# Connectors_and_mechanical.net
KiCad netlist of a schematic drawn in Altium Designer
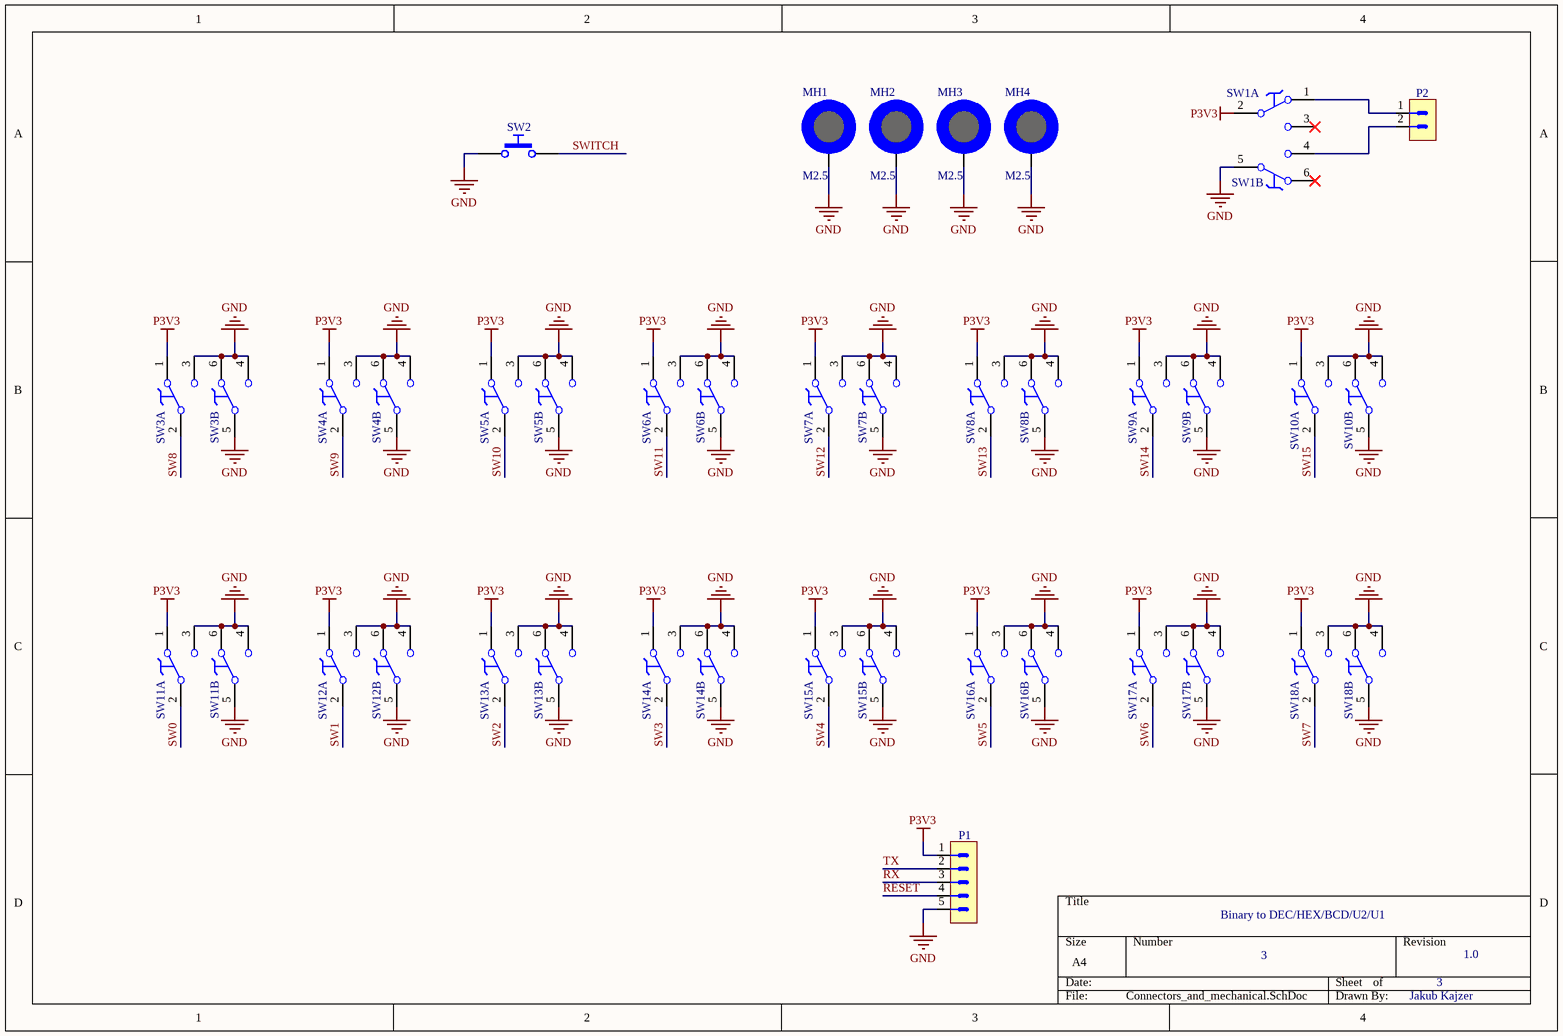
[diagram p0: Connectors_and_mechanical.SchDoc]

(export (version "E")
  (design (tool "Eeschema 10.0.6"))
  (components
    (comp (ref "MH1")
      (value "M2.5")
      (footprint "MH-M2.5_COPPER")
      (description "Mounting hole, M2.5, exposed pad")
      (fields (field (name "AUTHOR") "KB"))
      (libsource (lib "Mechanical And PCB Features") (part "MH"))
    )
    (comp (ref "MH2")
      (value "M2.5")
      (footprint "MH-M2.5_COPPER")
      (description "Mounting hole, M2.5, exposed pad")
      (fields (field (name "AUTHOR") "KB"))
      (libsource (lib "Mechanical And PCB Features") (part "MH"))
    )
    (comp (ref "MH3")
      (value "M2.5")
      (footprint "MH-M2.5_COPPER")
      (description "Mounting hole, M2.5, exposed pad")
      (fields (field (name "AUTHOR") "KB"))
      (libsource (lib "Mechanical And PCB Features") (part "MH"))
    )
    (comp (ref "MH4")
      (value "M2.5")
      (footprint "MH-M2.5_COPPER")
      (description "Mounting hole, M2.5, exposed pad")
      (fields (field (name "AUTHOR") "KB"))
      (libsource (lib "Mechanical And PCB Features") (part "MH"))
    )
    (comp (ref "P1")
      (value "SSW-105-02-G-S")
      (footprint "SAMTEC_SSW-105-02-G-S")
      (description "General Purpose Header: THT, 2.54mm, Female, Straight, Long Lead")
      (fields
        (field (name "MANUFACTURER") "GENERIC")
        (field (name "MANUFACTURER PART NUMBER") "HDR_THT_5X1V_F_2P54MM")
        (field (name "AUTHOR") "UN")
      )
      (libsource (lib "Connectors") (part "Header 5x1"))
    )
    (comp (ref "P2")
      (value "MTLW-102-07-G-S-250")
      (footprint "SAMTEC_MTLW-102-07-G-S-250")
      (description "General Purpose Header: THT, 2.54mm, Male, Straight")
      (fields
        (field (name "MANUFACTURER") "GENERIC")
        (field (name "MANUFACTURER PART NUMBER") "HDR_THT_2X1V_M_2P54MM")
        (field (name "AUTHOR") "PC")
      )
      (libsource (lib "Connectors") (part "Header 2x1"))
    )
    (comp (ref "SW1")
      (value "SS008B")
      (footprint "SS008B-02P-22")
      (description "Switch  2 position; DPDT; 0,3A/30VDC; ON-ON; 50mŁ[")
      (fields
        (field (name "MANUFACTURER") "CANAL ELECTRONIC")
        (field (name "MANUFACTURER PART NUMBER") "SS008B-02P-22")
        (field (name "AUTHOR") "JK")
      )
      (libsource (lib "") (part "SW DPDT 1NC-2C-3NO-4NO-5C-6NC_1"))
    )
    (comp (ref "SW2")
      (value "PTS636")
      (footprint "PTS636_SMT_G")
      (description "Tactile Switches Tact 50mA 12VDC, 6.0x3.5, 4.3mm H, 180gf, G leads, No ground pin, Black Actuator")
      (fields
        (field (name "MANUFACTURER") "C&K")
        (field (name "MANUFACTURER PART NUMBER") "PTS636 SM43 SMTR LFS")
        (field (name "AUTHOR") "KB")
      )
      (libsource (lib "Relays And Switches") (part "PB SPST 1NO-2NO"))
    )
    (comp (ref "SW3")
      (value "SS008B")
      (footprint "SS008B-02P-22")
      (description "Switch  2 position; DPDT; 0,3A/30VDC; ON-ON; 50mŁ[")
      (fields
        (field (name "MANUFACTURER") "CANAL ELECTRONIC")
        (field (name "MANUFACTURER PART NUMBER") "SS008B-02P-22")
        (field (name "AUTHOR") "JK")
      )
      (libsource (lib "Relays And Switches") (part "SW DPDT 1NC-2C-3NO-4NO-5C-6NC"))
    )
    (comp (ref "SW4")
      (value "SS008B")
      (footprint "SS008B-02P-22")
      (description "Switch  2 position; DPDT; 0,3A/30VDC; ON-ON; 50mŁ[")
      (fields
        (field (name "MANUFACTURER") "CANAL ELECTRONIC")
        (field (name "MANUFACTURER PART NUMBER") "SS008B-02P-22")
        (field (name "AUTHOR") "JK")
      )
      (libsource (lib "") (part "SW DPDT 1NC-2C-3NO-4NO-5C-6NC_2"))
    )
    (comp (ref "SW5")
      (value "SS008B")
      (footprint "SS008B-02P-22")
      (description "Switch  2 position; DPDT; 0,3A/30VDC; ON-ON; 50mŁ[")
      (fields
        (field (name "MANUFACTURER") "CANAL ELECTRONIC")
        (field (name "MANUFACTURER PART NUMBER") "SS008B-02P-22")
        (field (name "AUTHOR") "JK")
      )
      (libsource (lib "") (part "SW DPDT 1NC-2C-3NO-4NO-5C-6NC_2"))
    )
    (comp (ref "SW6")
      (value "SS008B")
      (footprint "SS008B-02P-22")
      (description "Switch  2 position; DPDT; 0,3A/30VDC; ON-ON; 50mŁ[")
      (fields
        (field (name "MANUFACTURER") "CANAL ELECTRONIC")
        (field (name "MANUFACTURER PART NUMBER") "SS008B-02P-22")
        (field (name "AUTHOR") "JK")
      )
      (libsource (lib "") (part "SW DPDT 1NC-2C-3NO-4NO-5C-6NC_2"))
    )
    (comp (ref "SW7")
      (value "SS008B")
      (footprint "SS008B-02P-22")
      (description "Switch  2 position; DPDT; 0,3A/30VDC; ON-ON; 50mŁ[")
      (fields
        (field (name "MANUFACTURER") "CANAL ELECTRONIC")
        (field (name "MANUFACTURER PART NUMBER") "SS008B-02P-22")
        (field (name "AUTHOR") "JK")
      )
      (libsource (lib "Relays And Switches") (part "SW DPDT 1NC-2C-3NO-4NO-5C-6NC"))
    )
    (comp (ref "SW8")
      (value "SS008B")
      (footprint "SS008B-02P-22")
      (description "Switch  2 position; DPDT; 0,3A/30VDC; ON-ON; 50mŁ[")
      (fields
        (field (name "MANUFACTURER") "CANAL ELECTRONIC")
        (field (name "MANUFACTURER PART NUMBER") "SS008B-02P-22")
        (field (name "AUTHOR") "JK")
      )
      (libsource (lib "Relays And Switches") (part "SW DPDT 1NC-2C-3NO-4NO-5C-6NC"))
    )
    (comp (ref "SW9")
      (value "SS008B")
      (footprint "SS008B-02P-22")
      (description "Switch  2 position; DPDT; 0,3A/30VDC; ON-ON; 50mŁ[")
      (fields
        (field (name "MANUFACTURER") "CANAL ELECTRONIC")
        (field (name "MANUFACTURER PART NUMBER") "SS008B-02P-22")
        (field (name "AUTHOR") "JK")
      )
      (libsource (lib "Relays And Switches") (part "SW DPDT 1NC-2C-3NO-4NO-5C-6NC"))
    )
    (comp (ref "SW10")
      (value "SS008B")
      (footprint "SS008B-02P-22")
      (description "Switch  2 position; DPDT; 0,3A/30VDC; ON-ON; 50mŁ[")
      (fields
        (field (name "MANUFACTURER") "CANAL ELECTRONIC")
        (field (name "MANUFACTURER PART NUMBER") "SS008B-02P-22")
        (field (name "AUTHOR") "JK")
      )
      (libsource (lib "Relays And Switches") (part "SW DPDT 1NC-2C-3NO-4NO-5C-6NC"))
    )
    (comp (ref "SW11")
      (value "SS008B")
      (footprint "SS008B-02P-22")
      (description "Switch  2 position; DPDT; 0,3A/30VDC; ON-ON; 50mŁ[")
      (fields
        (field (name "MANUFACTURER") "CANAL ELECTRONIC")
        (field (name "MANUFACTURER PART NUMBER") "SS008B-02P-22")
        (field (name "AUTHOR") "JK")
      )
      (libsource (lib "") (part "SW DPDT 1NC-2C-3NO-4NO-5C-6NC_2"))
    )
    (comp (ref "SW12")
      (value "SS008B")
      (footprint "SS008B-02P-22")
      (description "Switch  2 position; DPDT; 0,3A/30VDC; ON-ON; 50mŁ[")
      (fields
        (field (name "MANUFACTURER") "CANAL ELECTRONIC")
        (field (name "MANUFACTURER PART NUMBER") "SS008B-02P-22")
        (field (name "AUTHOR") "JK")
      )
      (libsource (lib "Relays And Switches") (part "SW DPDT 1NC-2C-3NO-4NO-5C-6NC"))
    )
    (comp (ref "SW13")
      (value "SS008B")
      (footprint "SS008B-02P-22")
      (description "Switch  2 position; DPDT; 0,3A/30VDC; ON-ON; 50mŁ[")
      (fields
        (field (name "MANUFACTURER") "CANAL ELECTRONIC")
        (field (name "MANUFACTURER PART NUMBER") "SS008B-02P-22")
        (field (name "AUTHOR") "JK")
      )
      (libsource (lib "") (part "SW DPDT 1NC-2C-3NO-4NO-5C-6NC_2"))
    )
    (comp (ref "SW14")
      (value "SS008B")
      (footprint "SS008B-02P-22")
      (description "Switch  2 position; DPDT; 0,3A/30VDC; ON-ON; 50mŁ[")
      (fields
        (field (name "MANUFACTURER") "CANAL ELECTRONIC")
        (field (name "MANUFACTURER PART NUMBER") "SS008B-02P-22")
        (field (name "AUTHOR") "JK")
      )
      (libsource (lib "") (part "SW DPDT 1NC-2C-3NO-4NO-5C-6NC_2"))
    )
    (comp (ref "SW15")
      (value "SS008B")
      (footprint "SS008B-02P-22")
      (description "Switch  2 position; DPDT; 0,3A/30VDC; ON-ON; 50mŁ[")
      (fields
        (field (name "MANUFACTURER") "CANAL ELECTRONIC")
        (field (name "MANUFACTURER PART NUMBER") "SS008B-02P-22")
        (field (name "AUTHOR") "JK")
      )
      (libsource (lib "Relays And Switches") (part "SW DPDT 1NC-2C-3NO-4NO-5C-6NC"))
    )
    (comp (ref "SW16")
      (value "SS008B")
      (footprint "SS008B-02P-22")
      (description "Switch  2 position; DPDT; 0,3A/30VDC; ON-ON; 50mŁ[")
      (fields
        (field (name "MANUFACTURER") "CANAL ELECTRONIC")
        (field (name "MANUFACTURER PART NUMBER") "SS008B-02P-22")
        (field (name "AUTHOR") "JK")
      )
      (libsource (lib "") (part "SW DPDT 1NC-2C-3NO-4NO-5C-6NC_2"))
    )
    (comp (ref "SW17")
      (value "SS008B")
      (footprint "SS008B-02P-22")
      (description "Switch  2 position; DPDT; 0,3A/30VDC; ON-ON; 50mŁ[")
      (fields
        (field (name "MANUFACTURER") "CANAL ELECTRONIC")
        (field (name "MANUFACTURER PART NUMBER") "SS008B-02P-22")
        (field (name "AUTHOR") "JK")
      )
      (libsource (lib "") (part "SW DPDT 1NC-2C-3NO-4NO-5C-6NC_2"))
    )
    (comp (ref "SW18")
      (value "SS008B")
      (footprint "SS008B-02P-22")
      (description "Switch  2 position; DPDT; 0,3A/30VDC; ON-ON; 50mŁ[")
      (fields
        (field (name "MANUFACTURER") "CANAL ELECTRONIC")
        (field (name "MANUFACTURER PART NUMBER") "SS008B-02P-22")
        (field (name "AUTHOR") "JK")
      )
      (libsource (lib "Relays And Switches") (part "SW DPDT 1NC-2C-3NO-4NO-5C-6NC"))
    )
  )
  (nets
    (net (code "1") (name "/RESET") (class "Default")
      (node (ref "P1") (pin "4") (pinfunction "4_4") (pintype "passive"))
    )
    (net (code "2") (name "/RX") (class "Default")
      (node (ref "P1") (pin "3") (pinfunction "3_3") (pintype "passive"))
    )
    (net (code "3") (name "/SW0") (class "Default")
      (node (ref "SW11") (pin "2") (pinfunction "2_2") (pintype "passive"))
    )
    (net (code "4") (name "/SW1") (class "Default")
      (node (ref "SW12") (pin "2") (pinfunction "2_2") (pintype "passive"))
    )
    (net (code "5") (name "/SW2") (class "Default")
      (node (ref "SW13") (pin "2") (pinfunction "2_2") (pintype "passive"))
    )
    (net (code "6") (name "/SW3") (class "Default")
      (node (ref "SW14") (pin "2") (pinfunction "2_2") (pintype "passive"))
    )
    (net (code "7") (name "/SW4") (class "Default")
      (node (ref "SW15") (pin "2") (pinfunction "2_2") (pintype "passive"))
    )
    (net (code "8") (name "/SW5") (class "Default")
      (node (ref "SW16") (pin "2") (pinfunction "2_2") (pintype "passive"))
    )
    (net (code "9") (name "/SW6") (class "Default")
      (node (ref "SW17") (pin "2") (pinfunction "2_2") (pintype "passive"))
    )
    (net (code "10") (name "/SW7") (class "Default")
      (node (ref "SW18") (pin "2") (pinfunction "2_2") (pintype "passive"))
    )
    (net (code "11") (name "/SW8") (class "Default")
      (node (ref "SW3") (pin "2") (pinfunction "2_2") (pintype "passive"))
    )
    (net (code "12") (name "/SW9") (class "Default")
      (node (ref "SW4") (pin "2") (pinfunction "2_2") (pintype "passive"))
    )
    (net (code "13") (name "/SW10") (class "Default")
      (node (ref "SW5") (pin "2") (pinfunction "2_2") (pintype "passive"))
    )
    (net (code "14") (name "/SW11") (class "Default")
      (node (ref "SW6") (pin "2") (pinfunction "2_2") (pintype "passive"))
    )
    (net (code "15") (name "/SW12") (class "Default")
      (node (ref "SW7") (pin "2") (pinfunction "2_2") (pintype "passive"))
    )
    (net (code "16") (name "/SW13") (class "Default")
      (node (ref "SW8") (pin "2") (pinfunction "2_2") (pintype "passive"))
    )
    (net (code "17") (name "/SW14") (class "Default")
      (node (ref "SW9") (pin "2") (pinfunction "2_2") (pintype "passive"))
    )
    (net (code "18") (name "/SW15") (class "Default")
      (node (ref "SW10") (pin "2") (pinfunction "2_2") (pintype "passive"))
    )
    (net (code "19") (name "/SWITCH") (class "Default")
      (node (ref "SW2") (pin "2") (pinfunction "2_2") (pintype "passive"))
    )
    (net (code "20") (name "/TX") (class "Default")
      (node (ref "P1") (pin "2") (pinfunction "2_2") (pintype "passive"))
    )
    (net (code "21") (name "GND") (class "Default")
      (node (ref "MH1") (pin "MH") (pinfunction "MH_MH") (pintype "passive"))
      (node (ref "MH2") (pin "MH") (pinfunction "MH_MH") (pintype "passive"))
      (node (ref "MH3") (pin "MH") (pinfunction "MH_MH") (pintype "passive"))
      (node (ref "MH4") (pin "MH") (pinfunction "MH_MH") (pintype "passive"))
      (node (ref "P1") (pin "5") (pinfunction "5_5") (pintype "passive"))
      (node (ref "SW1") (pin "5") (pinfunction "5_5") (pintype "passive"))
      (node (ref "SW10") (pin "3") (pinfunction "3_3") (pintype "passive"))
      (node (ref "SW10") (pin "4") (pinfunction "4_4") (pintype "passive"))
      (node (ref "SW10") (pin "5") (pinfunction "5_5") (pintype "passive"))
      (node (ref "SW10") (pin "6") (pinfunction "6_6") (pintype "passive"))
      (node (ref "SW11") (pin "3") (pinfunction "3_3") (pintype "passive"))
      (node (ref "SW11") (pin "4") (pinfunction "4_4") (pintype "passive"))
      (node (ref "SW11") (pin "5") (pinfunction "5_5") (pintype "passive"))
      (node (ref "SW11") (pin "6") (pinfunction "6_6") (pintype "passive"))
      (node (ref "SW12") (pin "3") (pinfunction "3_3") (pintype "passive"))
      (node (ref "SW12") (pin "4") (pinfunction "4_4") (pintype "passive"))
      (node (ref "SW12") (pin "5") (pinfunction "5_5") (pintype "passive"))
      (node (ref "SW12") (pin "6") (pinfunction "6_6") (pintype "passive"))
      (node (ref "SW13") (pin "3") (pinfunction "3_3") (pintype "passive"))
      (node (ref "SW13") (pin "4") (pinfunction "4_4") (pintype "passive"))
      (node (ref "SW13") (pin "5") (pinfunction "5_5") (pintype "passive"))
      (node (ref "SW13") (pin "6") (pinfunction "6_6") (pintype "passive"))
      (node (ref "SW14") (pin "3") (pinfunction "3_3") (pintype "passive"))
      (node (ref "SW14") (pin "4") (pinfunction "4_4") (pintype "passive"))
      (node (ref "SW14") (pin "5") (pinfunction "5_5") (pintype "passive"))
      (node (ref "SW14") (pin "6") (pinfunction "6_6") (pintype "passive"))
      (node (ref "SW15") (pin "3") (pinfunction "3_3") (pintype "passive"))
      (node (ref "SW15") (pin "4") (pinfunction "4_4") (pintype "passive"))
      (node (ref "SW15") (pin "5") (pinfunction "5_5") (pintype "passive"))
      (node (ref "SW15") (pin "6") (pinfunction "6_6") (pintype "passive"))
      (node (ref "SW16") (pin "3") (pinfunction "3_3") (pintype "passive"))
      (node (ref "SW16") (pin "4") (pinfunction "4_4") (pintype "passive"))
      (node (ref "SW16") (pin "5") (pinfunction "5_5") (pintype "passive"))
      (node (ref "SW16") (pin "6") (pinfunction "6_6") (pintype "passive"))
      (node (ref "SW17") (pin "3") (pinfunction "3_3") (pintype "passive"))
      (node (ref "SW17") (pin "4") (pinfunction "4_4") (pintype "passive"))
      (node (ref "SW17") (pin "5") (pinfunction "5_5") (pintype "passive"))
      (node (ref "SW17") (pin "6") (pinfunction "6_6") (pintype "passive"))
      (node (ref "SW18") (pin "3") (pinfunction "3_3") (pintype "passive"))
      (node (ref "SW18") (pin "4") (pinfunction "4_4") (pintype "passive"))
      (node (ref "SW18") (pin "5") (pinfunction "5_5") (pintype "passive"))
      (node (ref "SW18") (pin "6") (pinfunction "6_6") (pintype "passive"))
      (node (ref "SW2") (pin "1") (pinfunction "1_1") (pintype "passive"))
      (node (ref "SW3") (pin "3") (pinfunction "3_3") (pintype "passive"))
      (node (ref "SW3") (pin "4") (pinfunction "4_4") (pintype "passive"))
      (node (ref "SW3") (pin "5") (pinfunction "5_5") (pintype "passive"))
      (node (ref "SW3") (pin "6") (pinfunction "6_6") (pintype "passive"))
      (node (ref "SW4") (pin "3") (pinfunction "3_3") (pintype "passive"))
      (node (ref "SW4") (pin "4") (pinfunction "4_4") (pintype "passive"))
      (node (ref "SW4") (pin "5") (pinfunction "5_5") (pintype "passive"))
      (node (ref "SW4") (pin "6") (pinfunction "6_6") (pintype "passive"))
      (node (ref "SW5") (pin "3") (pinfunction "3_3") (pintype "passive"))
      (node (ref "SW5") (pin "4") (pinfunction "4_4") (pintype "passive"))
      (node (ref "SW5") (pin "5") (pinfunction "5_5") (pintype "passive"))
      (node (ref "SW5") (pin "6") (pinfunction "6_6") (pintype "passive"))
      (node (ref "SW6") (pin "3") (pinfunction "3_3") (pintype "passive"))
      (node (ref "SW6") (pin "4") (pinfunction "4_4") (pintype "passive"))
      (node (ref "SW6") (pin "5") (pinfunction "5_5") (pintype "passive"))
      (node (ref "SW6") (pin "6") (pinfunction "6_6") (pintype "passive"))
      (node (ref "SW7") (pin "3") (pinfunction "3_3") (pintype "passive"))
      (node (ref "SW7") (pin "4") (pinfunction "4_4") (pintype "passive"))
      (node (ref "SW7") (pin "5") (pinfunction "5_5") (pintype "passive"))
      (node (ref "SW7") (pin "6") (pinfunction "6_6") (pintype "passive"))
      (node (ref "SW8") (pin "3") (pinfunction "3_3") (pintype "passive"))
      (node (ref "SW8") (pin "4") (pinfunction "4_4") (pintype "passive"))
      (node (ref "SW8") (pin "5") (pinfunction "5_5") (pintype "passive"))
      (node (ref "SW8") (pin "6") (pinfunction "6_6") (pintype "passive"))
      (node (ref "SW9") (pin "3") (pinfunction "3_3") (pintype "passive"))
      (node (ref "SW9") (pin "4") (pinfunction "4_4") (pintype "passive"))
      (node (ref "SW9") (pin "5") (pinfunction "5_5") (pintype "passive"))
      (node (ref "SW9") (pin "6") (pinfunction "6_6") (pintype "passive"))
    )
    (net (code "22") (name "Net-(P2-Pad1)") (class "Default")
      (node (ref "P2") (pin "1") (pinfunction "1_1") (pintype "passive"))
      (node (ref "SW1") (pin "1") (pinfunction "1_1") (pintype "passive"))
    )
    (net (code "23") (name "Net-(P2-Pad2)") (class "Default")
      (node (ref "P2") (pin "2") (pinfunction "2_2") (pintype "passive"))
      (node (ref "SW1") (pin "4") (pinfunction "4_4") (pintype "passive"))
    )
    (net (code "24") (name "P3V3") (class "Default")
      (node (ref "P1") (pin "1") (pinfunction "1_1") (pintype "passive"))
      (node (ref "SW1") (pin "2") (pinfunction "2_2") (pintype "passive"))
      (node (ref "SW10") (pin "1") (pinfunction "1_1") (pintype "passive"))
      (node (ref "SW11") (pin "1") (pinfunction "1_1") (pintype "passive"))
      (node (ref "SW12") (pin "1") (pinfunction "1_1") (pintype "passive"))
      (node (ref "SW13") (pin "1") (pinfunction "1_1") (pintype "passive"))
      (node (ref "SW14") (pin "1") (pinfunction "1_1") (pintype "passive"))
      (node (ref "SW15") (pin "1") (pinfunction "1_1") (pintype "passive"))
      (node (ref "SW16") (pin "1") (pinfunction "1_1") (pintype "passive"))
      (node (ref "SW17") (pin "1") (pinfunction "1_1") (pintype "passive"))
      (node (ref "SW18") (pin "1") (pinfunction "1_1") (pintype "passive"))
      (node (ref "SW3") (pin "1") (pinfunction "1_1") (pintype "passive"))
      (node (ref "SW4") (pin "1") (pinfunction "1_1") (pintype "passive"))
      (node (ref "SW5") (pin "1") (pinfunction "1_1") (pintype "passive"))
      (node (ref "SW6") (pin "1") (pinfunction "1_1") (pintype "passive"))
      (node (ref "SW7") (pin "1") (pinfunction "1_1") (pintype "passive"))
      (node (ref "SW8") (pin "1") (pinfunction "1_1") (pintype "passive"))
      (node (ref "SW9") (pin "1") (pinfunction "1_1") (pintype "passive"))
    )
    (net (code "25") (name "unconnected-(SW1-Pad3)") (class "Default")
      (node (ref "SW1") (pin "3") (pinfunction "3_3") (pintype "passive+no_connect"))
    )
    (net (code "26") (name "unconnected-(SW1-Pad6)") (class "Default")
      (node (ref "SW1") (pin "6") (pinfunction "6_6") (pintype "passive+no_connect"))
    )
  )
)
